# decoder.net
KiCad netlist of a schematic drawn in EAGLE
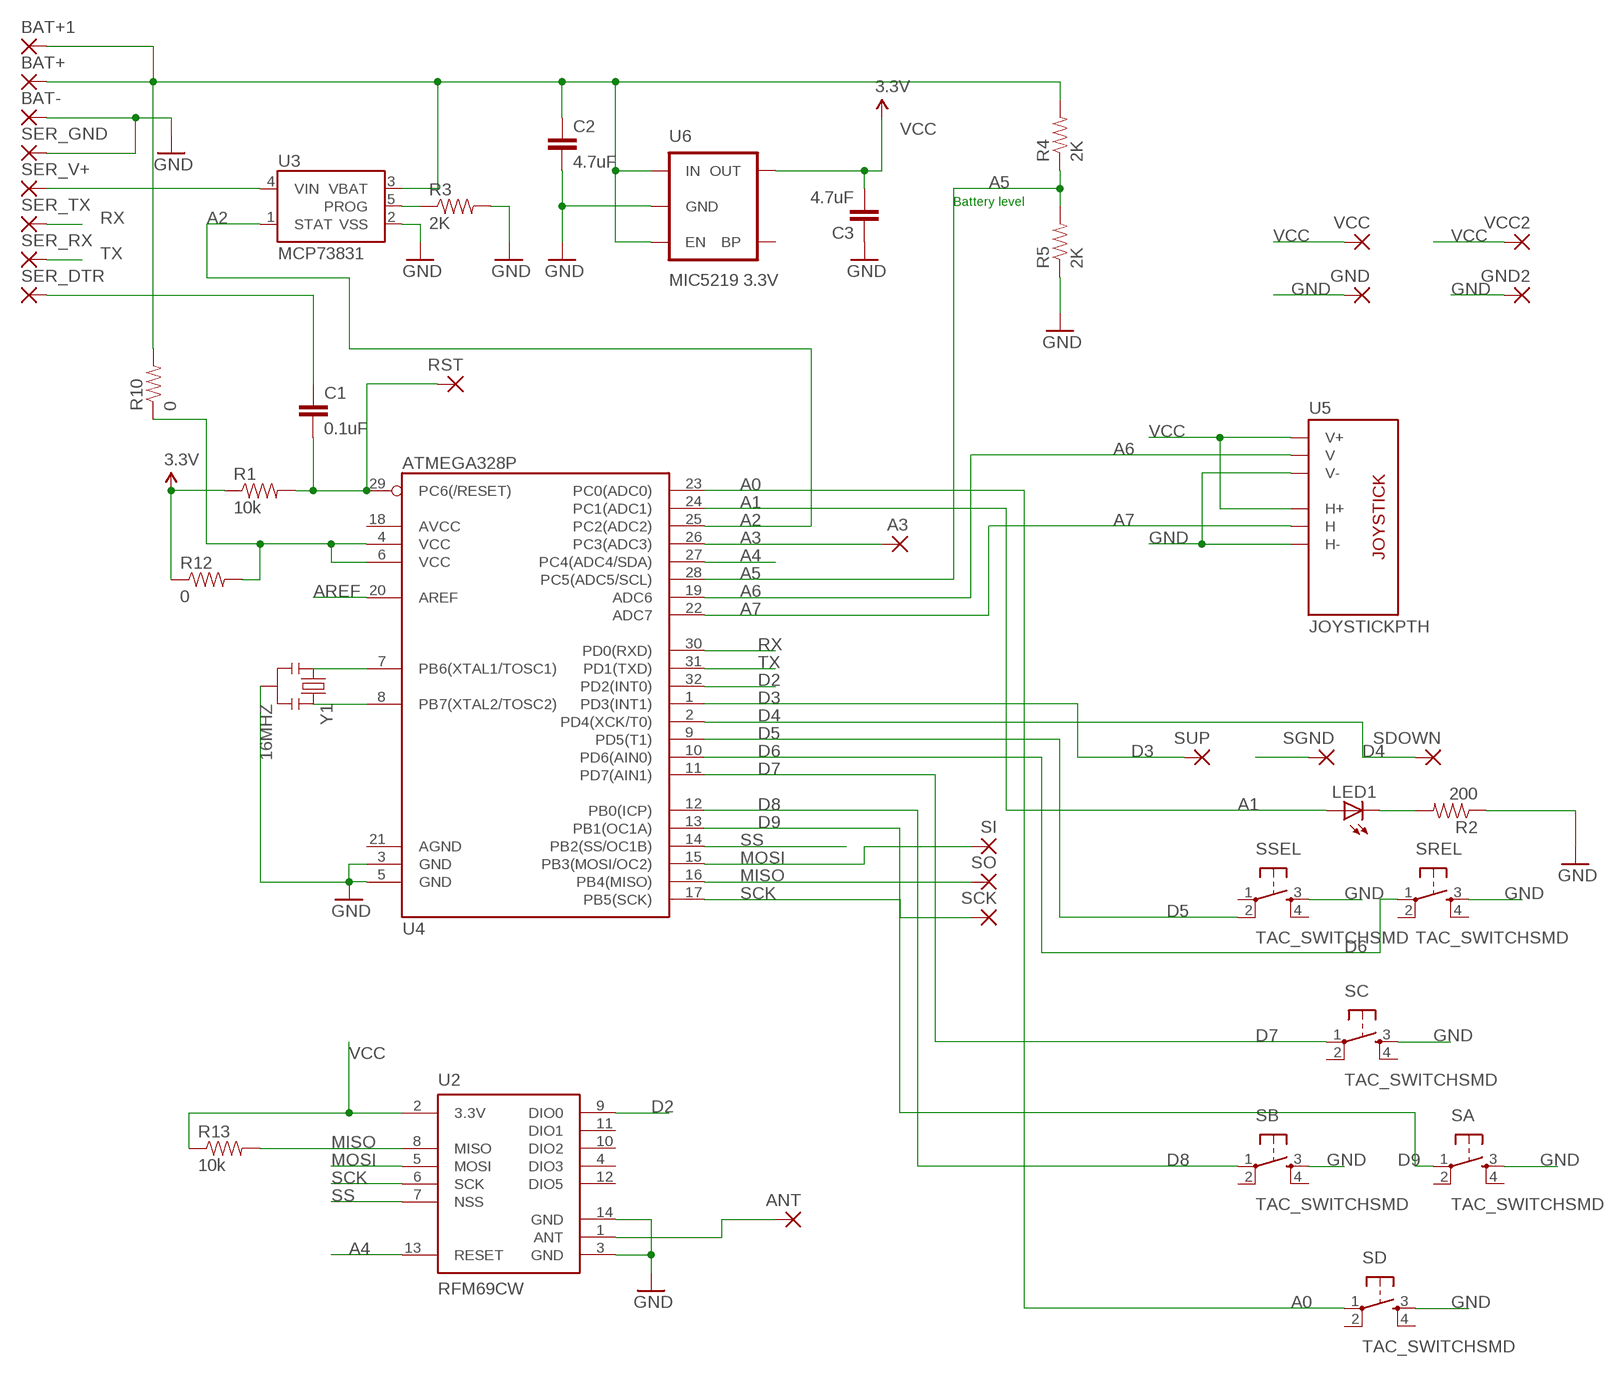
[diagram p0: schematic, sheet 1]

(export (version "E")
  (design (tool "Eeschema 10.0.6"))
  (components
    (comp (ref "A3")
      (value "SMD2")
      (footprint "eagle-import:SMD1,27-2,54")
      (libsource (lib "eagle-import") (part "SMD2"))
    )
    (comp (ref "ANT")
      (value "SMD2")
      (footprint "eagle-import:SMD1,27-2,54")
      (libsource (lib "eagle-import") (part "SMD2"))
    )
    (comp (ref "BAT+")
      (value "SMD2")
      (footprint "eagle-import:SMD1,27-2,54")
      (libsource (lib "eagle-import") (part "SMD2"))
    )
    (comp (ref "BAT+1")
      (value "SMD2")
      (footprint "eagle-import:SMD1,27-2,54")
      (libsource (lib "eagle-import") (part "SMD2"))
    )
    (comp (ref "BAT-")
      (value "SMD2")
      (footprint "eagle-import:SMD1,27-2,54")
      (libsource (lib "eagle-import") (part "SMD2"))
    )
    (comp (ref "C1")
      (value "0.1uF")
      (footprint "eagle-import:0805")
      (libsource (lib "eagle-import") (part "CAP0805"))
    )
    (comp (ref "C2")
      (value "4.7uF")
      (footprint "eagle-import:0805")
      (libsource (lib "eagle-import") (part "CAP0805"))
    )
    (comp (ref "C3")
      (value "4.7uF")
      (footprint "eagle-import:0805")
      (libsource (lib "eagle-import") (part "CAP0805"))
    )
    (comp (ref "GND")
      (value "SMD2")
      (footprint "eagle-import:SMD1,27-2,54")
      (libsource (lib "eagle-import") (part "SMD2"))
    )
    (comp (ref "GND2")
      (value "SMD2")
      (footprint "eagle-import:SMD1,27-2,54")
      (libsource (lib "eagle-import") (part "SMD2"))
    )
    (comp (ref "LED1")
      (value "LED3MM")
      (footprint "eagle-import:LED3MM")
      (libsource (lib "eagle-import") (part "LED3MM"))
    )
    (comp (ref "R1")
      (value "10k")
      (footprint "eagle-import:0603-RES")
      (libsource (lib "eagle-import") (part "RESISTOR0603-RES"))
    )
    (comp (ref "R2")
      (value "200")
      (footprint "eagle-import:0603-RES")
      (libsource (lib "eagle-import") (part "RESISTOR0603-RES"))
    )
    (comp (ref "R3")
      (value "2K")
      (footprint "eagle-import:0603-RES")
      (libsource (lib "eagle-import") (part "RESISTOR0603-RES"))
    )
    (comp (ref "R4")
      (value "2K")
      (footprint "eagle-import:0603-RES")
      (libsource (lib "eagle-import") (part "RESISTOR0603-RES"))
    )
    (comp (ref "R5")
      (value "2K")
      (footprint "eagle-import:0603-RES")
      (libsource (lib "eagle-import") (part "RESISTOR0603-RES"))
    )
    (comp (ref "R10")
      (value "0")
      (footprint "eagle-import:0603-RES")
      (libsource (lib "eagle-import") (part "RESISTOR0603-RES"))
    )
    (comp (ref "R12")
      (value "0")
      (footprint "eagle-import:0603-RES")
      (libsource (lib "eagle-import") (part "RESISTOR0603-RES"))
    )
    (comp (ref "R13")
      (value "10k")
      (footprint "eagle-import:0603-RES")
      (libsource (lib "eagle-import") (part "RESISTOR0603-RES"))
    )
    (comp (ref "RST")
      (value "SMD2")
      (footprint "eagle-import:SMD1,27-2,54")
      (libsource (lib "eagle-import") (part "SMD2"))
    )
    (comp (ref "SA")
      (value "TAC_SWITCHSMD")
      (footprint "eagle-import:TACTILE-SWITCH-SMD")
      (libsource (lib "eagle-import") (part "TAC_SWITCHSMD"))
    )
    (comp (ref "SB")
      (value "TAC_SWITCHSMD")
      (footprint "eagle-import:TACTILE-SWITCH-SMD")
      (libsource (lib "eagle-import") (part "TAC_SWITCHSMD"))
    )
    (comp (ref "SC")
      (value "TAC_SWITCHSMD")
      (footprint "eagle-import:TACTILE-SWITCH-SMD")
      (libsource (lib "eagle-import") (part "TAC_SWITCHSMD"))
    )
    (comp (ref "SCK")
      (value "SMD2")
      (footprint "eagle-import:SMD1,27-2,54")
      (libsource (lib "eagle-import") (part "SMD2"))
    )
    (comp (ref "SD")
      (value "TAC_SWITCHSMD")
      (footprint "eagle-import:TACTILE-SWITCH-SMD")
      (libsource (lib "eagle-import") (part "TAC_SWITCHSMD"))
    )
    (comp (ref "SDOWN")
      (value "SMD2")
      (footprint "eagle-import:SMD1,27-2,54")
      (libsource (lib "eagle-import") (part "SMD2"))
    )
    (comp (ref "SER_DTR")
      (value "SMD2")
      (footprint "eagle-import:SMD1,27-2,54")
      (libsource (lib "eagle-import") (part "SMD2"))
    )
    (comp (ref "SER_GND")
      (value "SMD2")
      (footprint "eagle-import:SMD1,27-2,54")
      (libsource (lib "eagle-import") (part "SMD2"))
    )
    (comp (ref "SER_RX")
      (value "SMD2")
      (footprint "eagle-import:SMD1,27-2,54")
      (libsource (lib "eagle-import") (part "SMD2"))
    )
    (comp (ref "SER_TX")
      (value "SMD2")
      (footprint "eagle-import:SMD1,27-2,54")
      (libsource (lib "eagle-import") (part "SMD2"))
    )
    (comp (ref "SER_V+")
      (value "SMD2")
      (footprint "eagle-import:SMD1,27-2,54")
      (libsource (lib "eagle-import") (part "SMD2"))
    )
    (comp (ref "SGND")
      (value "SMD2")
      (footprint "eagle-import:SMD1,27-2,54")
      (libsource (lib "eagle-import") (part "SMD2"))
    )
    (comp (ref "SI")
      (value "SMD2")
      (footprint "eagle-import:SMD1,27-2,54")
      (libsource (lib "eagle-import") (part "SMD2"))
    )
    (comp (ref "SO")
      (value "SMD2")
      (footprint "eagle-import:SMD1,27-2,54")
      (libsource (lib "eagle-import") (part "SMD2"))
    )
    (comp (ref "SREL")
      (value "TAC_SWITCHSMD")
      (footprint "eagle-import:TACTILE-SWITCH-SMD")
      (libsource (lib "eagle-import") (part "TAC_SWITCHSMD"))
    )
    (comp (ref "SSEL")
      (value "TAC_SWITCHSMD")
      (footprint "eagle-import:TACTILE-SWITCH-SMD")
      (libsource (lib "eagle-import") (part "TAC_SWITCHSMD"))
    )
    (comp (ref "SUP")
      (value "SMD2")
      (footprint "eagle-import:SMD1,27-2,54")
      (libsource (lib "eagle-import") (part "SMD2"))
    )
    (comp (ref "U2")
      (value "RFM69CW")
      (footprint "eagle-import:RFM69CW-XXXS2")
      (libsource (lib "eagle-import") (part "RFM69CW"))
    )
    (comp (ref "U3")
      (value "MCP73831")
      (footprint "eagle-import:SOT23-5")
      (libsource (lib "eagle-import") (part "MCP73831"))
    )
    (comp (ref "U4")
      (value "ATMEGA328P")
      (footprint "eagle-import:TQFP32-08")
      (libsource (lib "eagle-import") (part "ATMEGA328_SMT"))
    )
    (comp (ref "U5")
      (value "JOYSTICKPTH")
      (footprint "eagle-import:JOYSTICK")
      (libsource (lib "eagle-import") (part "JOYSTICKPTH"))
    )
    (comp (ref "U6")
      (value "MIC5219 3.3V")
      (footprint "eagle-import:SOT23-5")
      (libsource (lib "eagle-import") (part "V_REG_MIC52193.3V"))
    )
    (comp (ref "VCC")
      (value "SMD2")
      (footprint "eagle-import:SMD1,27-2,54")
      (libsource (lib "eagle-import") (part "SMD2"))
    )
    (comp (ref "VCC2")
      (value "SMD2")
      (footprint "eagle-import:SMD1,27-2,54")
      (libsource (lib "eagle-import") (part "SMD2"))
    )
    (comp (ref "Y1")
      (value "16MHZ")
      (footprint "eagle-import:RESONATOR-SMD")
      (libsource (lib "eagle-import") (part "RESONATOR16MHZ"))
    )
  )
  (nets
    (net (code "1") (name "/A0") (class "Default")
      (node (ref "SD") (pin "1") (pinfunction "1_1") (pintype "passive"))
      (node (ref "U4") (pin "23") (pinfunction "PC0(ADC0)_23") (pintype "bidirectional"))
    )
    (net (code "2") (name "/A1") (class "Default")
      (node (ref "LED1") (pin "A") (pinfunction "A_A") (pintype "passive"))
      (node (ref "U4") (pin "24") (pinfunction "PC1(ADC1)_24") (pintype "bidirectional"))
    )
    (net (code "3") (name "/A2") (class "Default")
      (node (ref "U3") (pin "1") (pinfunction "STAT_1") (pintype "output"))
      (node (ref "U4") (pin "25") (pinfunction "PC2(ADC2)_25") (pintype "bidirectional"))
    )
    (net (code "4") (name "/A3") (class "Default")
      (node (ref "A3") (pin "1") (pinfunction "P_1") (pintype "passive"))
      (node (ref "U4") (pin "26") (pinfunction "PC3(ADC3)_26") (pintype "bidirectional"))
    )
    (net (code "5") (name "/A4") (class "Default")
      (node (ref "U2") (pin "13") (pinfunction "RESET_13") (pintype "input"))
      (node (ref "U4") (pin "27") (pinfunction "PC4(ADC4/SDA)_27") (pintype "bidirectional"))
    )
    (net (code "6") (name "/A5") (class "Default")
      (node (ref "R4") (pin "1") (pinfunction "1_1") (pintype "passive"))
      (node (ref "R5") (pin "2") (pinfunction "2_2") (pintype "passive"))
      (node (ref "U4") (pin "28") (pinfunction "PC5(ADC5/SCL)_28") (pintype "bidirectional"))
    )
    (net (code "7") (name "/A6") (class "Default")
      (node (ref "U4") (pin "19") (pinfunction "ADC6_19") (pintype "bidirectional"))
      (node (ref "U5") (pin "V2") (pinfunction "V_V2") (pintype "bidirectional"))
    )
    (net (code "8") (name "/A7") (class "Default")
      (node (ref "U4") (pin "22") (pinfunction "ADC7_22") (pintype "bidirectional"))
      (node (ref "U5") (pin "H2") (pinfunction "H_H2") (pintype "bidirectional"))
    )
    (net (code "9") (name "/AREF") (class "Default")
      (node (ref "U4") (pin "20") (pinfunction "AREF_20") (pintype "bidirectional"))
    )
    (net (code "10") (name "/D2") (class "Default")
      (node (ref "U2") (pin "9") (pinfunction "DIO0_9") (pintype "bidirectional"))
      (node (ref "U4") (pin "32") (pinfunction "PD2(INT0)_32") (pintype "bidirectional"))
    )
    (net (code "11") (name "/D3") (class "Default")
      (node (ref "SUP") (pin "1") (pinfunction "P_1") (pintype "passive"))
      (node (ref "U4") (pin "1") (pinfunction "PD3(INT1)_1") (pintype "bidirectional"))
    )
    (net (code "12") (name "/D4") (class "Default")
      (node (ref "SDOWN") (pin "1") (pinfunction "P_1") (pintype "passive"))
      (node (ref "U4") (pin "2") (pinfunction "PD4(XCK/T0)_2") (pintype "bidirectional"))
    )
    (net (code "13") (name "/D5") (class "Default")
      (node (ref "SSEL") (pin "2") (pinfunction "2_2") (pintype "passive"))
      (node (ref "U4") (pin "9") (pinfunction "PD5(T1)_9") (pintype "bidirectional"))
    )
    (net (code "14") (name "/D6") (class "Default")
      (node (ref "SREL") (pin "1") (pinfunction "1_1") (pintype "passive"))
      (node (ref "U4") (pin "10") (pinfunction "PD6(AIN0)_10") (pintype "bidirectional"))
    )
    (net (code "15") (name "/D7") (class "Default")
      (node (ref "SC") (pin "1") (pinfunction "1_1") (pintype "passive"))
      (node (ref "U4") (pin "11") (pinfunction "PD7(AIN1)_11") (pintype "bidirectional"))
    )
    (net (code "16") (name "/D8") (class "Default")
      (node (ref "SB") (pin "1") (pinfunction "1_1") (pintype "passive"))
      (node (ref "U4") (pin "12") (pinfunction "PB0(ICP)_12") (pintype "bidirectional"))
    )
    (net (code "17") (name "/D9") (class "Default")
      (node (ref "SA") (pin "1") (pinfunction "1_1") (pintype "passive"))
      (node (ref "U4") (pin "13") (pinfunction "PB1(OC1A)_13") (pintype "bidirectional"))
    )
    (net (code "18") (name "/MISO") (class "Default")
      (node (ref "R13") (pin "2") (pinfunction "2_2") (pintype "passive"))
      (node (ref "SO") (pin "1") (pinfunction "P_1") (pintype "passive"))
      (node (ref "U2") (pin "8") (pinfunction "MISO_8") (pintype "bidirectional"))
      (node (ref "U4") (pin "16") (pinfunction "PB4(MISO)_16") (pintype "bidirectional"))
    )
    (net (code "19") (name "/MOSI") (class "Default")
      (node (ref "SI") (pin "1") (pinfunction "P_1") (pintype "passive"))
      (node (ref "U2") (pin "5") (pinfunction "MOSI_5") (pintype "input"))
      (node (ref "U4") (pin "15") (pinfunction "PB3(MOSI/OC2)_15") (pintype "bidirectional"))
    )
    (net (code "20") (name "/RX") (class "Default")
      (node (ref "SER_TX") (pin "1") (pinfunction "P_1") (pintype "passive"))
      (node (ref "U4") (pin "30") (pinfunction "PD0(RXD)_30") (pintype "bidirectional"))
    )
    (net (code "21") (name "/SCK") (class "Default")
      (node (ref "SCK") (pin "1") (pinfunction "P_1") (pintype "passive"))
      (node (ref "U2") (pin "6") (pinfunction "SCK_6") (pintype "input"))
      (node (ref "U4") (pin "17") (pinfunction "PB5(SCK)_17") (pintype "bidirectional"))
    )
    (net (code "22") (name "/SS") (class "Default")
      (node (ref "U2") (pin "7") (pinfunction "NSS_7") (pintype "input"))
      (node (ref "U4") (pin "14") (pinfunction "PB2(SS/OC1B)_14") (pintype "bidirectional"))
    )
    (net (code "23") (name "/TX") (class "Default")
      (node (ref "SER_RX") (pin "1") (pinfunction "P_1") (pintype "passive"))
      (node (ref "U4") (pin "31") (pinfunction "PD1(TXD)_31") (pintype "bidirectional"))
    )
    (net (code "24") (name "3.3V") (class "Default")
      (node (ref "C3") (pin "2") (pinfunction "2_2") (pintype "passive"))
      (node (ref "R1") (pin "1") (pinfunction "1_1") (pintype "passive"))
      (node (ref "R12") (pin "1") (pinfunction "1_1") (pintype "passive"))
      (node (ref "R13") (pin "1") (pinfunction "1_1") (pintype "passive"))
      (node (ref "U2") (pin "2") (pinfunction "3.3V_2") (pintype "power_in"))
      (node (ref "U5") (pin "H1") (pinfunction "H+_H1") (pintype "bidirectional"))
      (node (ref "U5") (pin "V1") (pinfunction "V+_V1") (pintype "bidirectional"))
      (node (ref "U6") (pin "5") (pinfunction "OUT_5") (pintype "passive"))
      (node (ref "VCC") (pin "1") (pinfunction "P_1") (pintype "passive"))
      (node (ref "VCC2") (pin "1") (pinfunction "P_1") (pintype "passive"))
    )
    (net (code "25") (name "GND") (class "Default")
      (node (ref "BAT-") (pin "1") (pinfunction "P_1") (pintype "passive"))
      (node (ref "C2") (pin "2") (pinfunction "2_2") (pintype "passive"))
      (node (ref "C3") (pin "1") (pinfunction "1_1") (pintype "passive"))
      (node (ref "GND") (pin "1") (pinfunction "P_1") (pintype "passive"))
      (node (ref "GND2") (pin "1") (pinfunction "P_1") (pintype "passive"))
      (node (ref "R2") (pin "1") (pinfunction "1_1") (pintype "passive"))
      (node (ref "R3") (pin "2") (pinfunction "2_2") (pintype "passive"))
      (node (ref "R5") (pin "1") (pinfunction "1_1") (pintype "passive"))
      (node (ref "SA") (pin "3") (pinfunction "3_3") (pintype "passive"))
      (node (ref "SB") (pin "3") (pinfunction "3_3") (pintype "passive"))
      (node (ref "SC") (pin "3") (pinfunction "3_3") (pintype "passive"))
      (node (ref "SD") (pin "3") (pinfunction "3_3") (pintype "passive"))
      (node (ref "SER_GND") (pin "1") (pinfunction "P_1") (pintype "passive"))
      (node (ref "SGND") (pin "1") (pinfunction "P_1") (pintype "passive"))
      (node (ref "SREL") (pin "3") (pinfunction "3_3") (pintype "passive"))
      (node (ref "SSEL") (pin "3") (pinfunction "3_3") (pintype "passive"))
      (node (ref "U2") (pin "14") (pinfunction "GND_14") (pintype "power_in"))
      (node (ref "U2") (pin "3") (pinfunction "GND_3") (pintype "power_in"))
      (node (ref "U3") (pin "2") (pinfunction "VSS_2") (pintype "power_in"))
      (node (ref "U4") (pin "3") (pinfunction "GND_3") (pintype "bidirectional"))
      (node (ref "U4") (pin "5") (pinfunction "GND_5") (pintype "bidirectional"))
      (node (ref "U5") (pin "H3") (pinfunction "H-_H3") (pintype "bidirectional"))
      (node (ref "U5") (pin "V3") (pinfunction "V-_V3") (pintype "bidirectional"))
      (node (ref "U6") (pin "2") (pinfunction "GND_2") (pintype "input"))
      (node (ref "Y1") (pin "2") (pinfunction "2_2") (pintype "passive"))
    )
    (net (code "26") (name "Net-(ANT-P)") (class "Default")
      (node (ref "ANT") (pin "1") (pinfunction "P_1") (pintype "passive"))
      (node (ref "U2") (pin "1") (pinfunction "ANT_1") (pintype "passive"))
    )
    (net (code "27") (name "Net-(BAT+-P)") (class "Default")
      (node (ref "BAT+") (pin "1") (pinfunction "P_1") (pintype "passive"))
      (node (ref "BAT+1") (pin "1") (pinfunction "P_1") (pintype "passive"))
      (node (ref "C2") (pin "1") (pinfunction "1_1") (pintype "passive"))
      (node (ref "R10") (pin "2") (pinfunction "2_2") (pintype "passive"))
      (node (ref "R4") (pin "2") (pinfunction "2_2") (pintype "passive"))
      (node (ref "U3") (pin "3") (pinfunction "VBAT_3") (pintype "power_in"))
      (node (ref "U6") (pin "1") (pinfunction "IN_1") (pintype "input"))
      (node (ref "U6") (pin "3") (pinfunction "EN_3") (pintype "input"))
    )
    (net (code "28") (name "Net-(LED1-C)") (class "Default")
      (node (ref "LED1") (pin "K") (pinfunction "C_K") (pintype "passive"))
      (node (ref "R2") (pin "2") (pinfunction "2_2") (pintype "passive"))
    )
    (net (code "29") (name "Net-(R10-Pad1)") (class "Default")
      (node (ref "R10") (pin "1") (pinfunction "1_1") (pintype "passive"))
      (node (ref "R12") (pin "2") (pinfunction "2_2") (pintype "passive"))
      (node (ref "U4") (pin "4") (pinfunction "VCC_4") (pintype "bidirectional"))
      (node (ref "U4") (pin "6") (pinfunction "VCC_6") (pintype "bidirectional"))
    )
    (net (code "30") (name "Net-(RST-P)") (class "Default")
      (node (ref "C1") (pin "2") (pinfunction "2_2") (pintype "passive"))
      (node (ref "R1") (pin "2") (pinfunction "2_2") (pintype "passive"))
      (node (ref "RST") (pin "1") (pinfunction "P_1") (pintype "passive"))
      (node (ref "U4") (pin "29") (pinfunction "PC6(/RESET)_29") (pintype "bidirectional"))
    )
    (net (code "31") (name "Net-(SER_DTR-P)") (class "Default")
      (node (ref "C1") (pin "1") (pinfunction "1_1") (pintype "passive"))
      (node (ref "SER_DTR") (pin "1") (pinfunction "P_1") (pintype "passive"))
    )
    (net (code "32") (name "Net-(SER_V+-P)") (class "Default")
      (node (ref "SER_V+") (pin "1") (pinfunction "P_1") (pintype "passive"))
      (node (ref "U3") (pin "4") (pinfunction "VIN_4") (pintype "power_in"))
    )
    (net (code "33") (name "Net-(U3-PROG)") (class "Default")
      (node (ref "R3") (pin "1") (pinfunction "1_1") (pintype "passive"))
      (node (ref "U3") (pin "5") (pinfunction "PROG_5") (pintype "input"))
    )
    (net (code "34") (name "Net-(U4-PB6(XTAL1{slash}TOSC1))") (class "Default")
      (node (ref "U4") (pin "7") (pinfunction "PB6(XTAL1/TOSC1)_7") (pintype "bidirectional"))
      (node (ref "Y1") (pin "1") (pinfunction "1_1") (pintype "passive"))
    )
    (net (code "35") (name "Net-(U4-PB7(XTAL2{slash}TOSC2))") (class "Default")
      (node (ref "U4") (pin "8") (pinfunction "PB7(XTAL2/TOSC2)_8") (pintype "bidirectional"))
      (node (ref "Y1") (pin "3") (pinfunction "3_3") (pintype "passive"))
    )
    (net (code "36") (name "unconnected-(SA-Pad2)") (class "Default")
      (node (ref "SA") (pin "2") (pinfunction "2_2") (pintype "passive"))
    )
    (net (code "37") (name "unconnected-(SA-Pad4)") (class "Default")
      (node (ref "SA") (pin "4") (pinfunction "4_4") (pintype "passive"))
    )
    (net (code "38") (name "unconnected-(SB-Pad2)") (class "Default")
      (node (ref "SB") (pin "2") (pinfunction "2_2") (pintype "passive"))
    )
    (net (code "39") (name "unconnected-(SB-Pad4)") (class "Default")
      (node (ref "SB") (pin "4") (pinfunction "4_4") (pintype "passive"))
    )
    (net (code "40") (name "unconnected-(SC-Pad2)") (class "Default")
      (node (ref "SC") (pin "2") (pinfunction "2_2") (pintype "passive"))
    )
    (net (code "41") (name "unconnected-(SC-Pad4)") (class "Default")
      (node (ref "SC") (pin "4") (pinfunction "4_4") (pintype "passive"))
    )
    (net (code "42") (name "unconnected-(SD-Pad2)") (class "Default")
      (node (ref "SD") (pin "2") (pinfunction "2_2") (pintype "passive"))
    )
    (net (code "43") (name "unconnected-(SD-Pad4)") (class "Default")
      (node (ref "SD") (pin "4") (pinfunction "4_4") (pintype "passive"))
    )
    (net (code "44") (name "unconnected-(SREL-Pad2)") (class "Default")
      (node (ref "SREL") (pin "2") (pinfunction "2_2") (pintype "passive"))
    )
    (net (code "45") (name "unconnected-(SREL-Pad4)") (class "Default")
      (node (ref "SREL") (pin "4") (pinfunction "4_4") (pintype "passive"))
    )
    (net (code "46") (name "unconnected-(SSEL-Pad1)") (class "Default")
      (node (ref "SSEL") (pin "1") (pinfunction "1_1") (pintype "passive"))
    )
    (net (code "47") (name "unconnected-(SSEL-Pad4)") (class "Default")
      (node (ref "SSEL") (pin "4") (pinfunction "4_4") (pintype "passive"))
    )
    (net (code "48") (name "unconnected-(U2-DIO1-Pad11)") (class "Default")
      (node (ref "U2") (pin "11") (pinfunction "DIO1_11") (pintype "bidirectional"))
    )
    (net (code "49") (name "unconnected-(U2-DIO2-Pad10)") (class "Default")
      (node (ref "U2") (pin "10") (pinfunction "DIO2_10") (pintype "bidirectional"))
    )
    (net (code "50") (name "unconnected-(U2-DIO3-Pad4)") (class "Default")
      (node (ref "U2") (pin "4") (pinfunction "DIO3_4") (pintype "bidirectional"))
    )
    (net (code "51") (name "unconnected-(U2-DIO5-Pad12)") (class "Default")
      (node (ref "U2") (pin "12") (pinfunction "DIO5_12") (pintype "bidirectional"))
    )
    (net (code "52") (name "unconnected-(U4-AGND-Pad21)") (class "Default")
      (node (ref "U4") (pin "21") (pinfunction "AGND_21") (pintype "bidirectional"))
    )
    (net (code "53") (name "unconnected-(U4-AVCC-Pad18)") (class "Default")
      (node (ref "U4") (pin "18") (pinfunction "AVCC_18") (pintype "bidirectional"))
    )
    (net (code "54") (name "unconnected-(U6-BP-Pad4)") (class "Default")
      (node (ref "U6") (pin "4") (pinfunction "BP_4") (pintype "input"))
    )
  )
)
